# SCH_AUDIO5822.net
KiCad netlist of a schematic drawn in EasyEDA
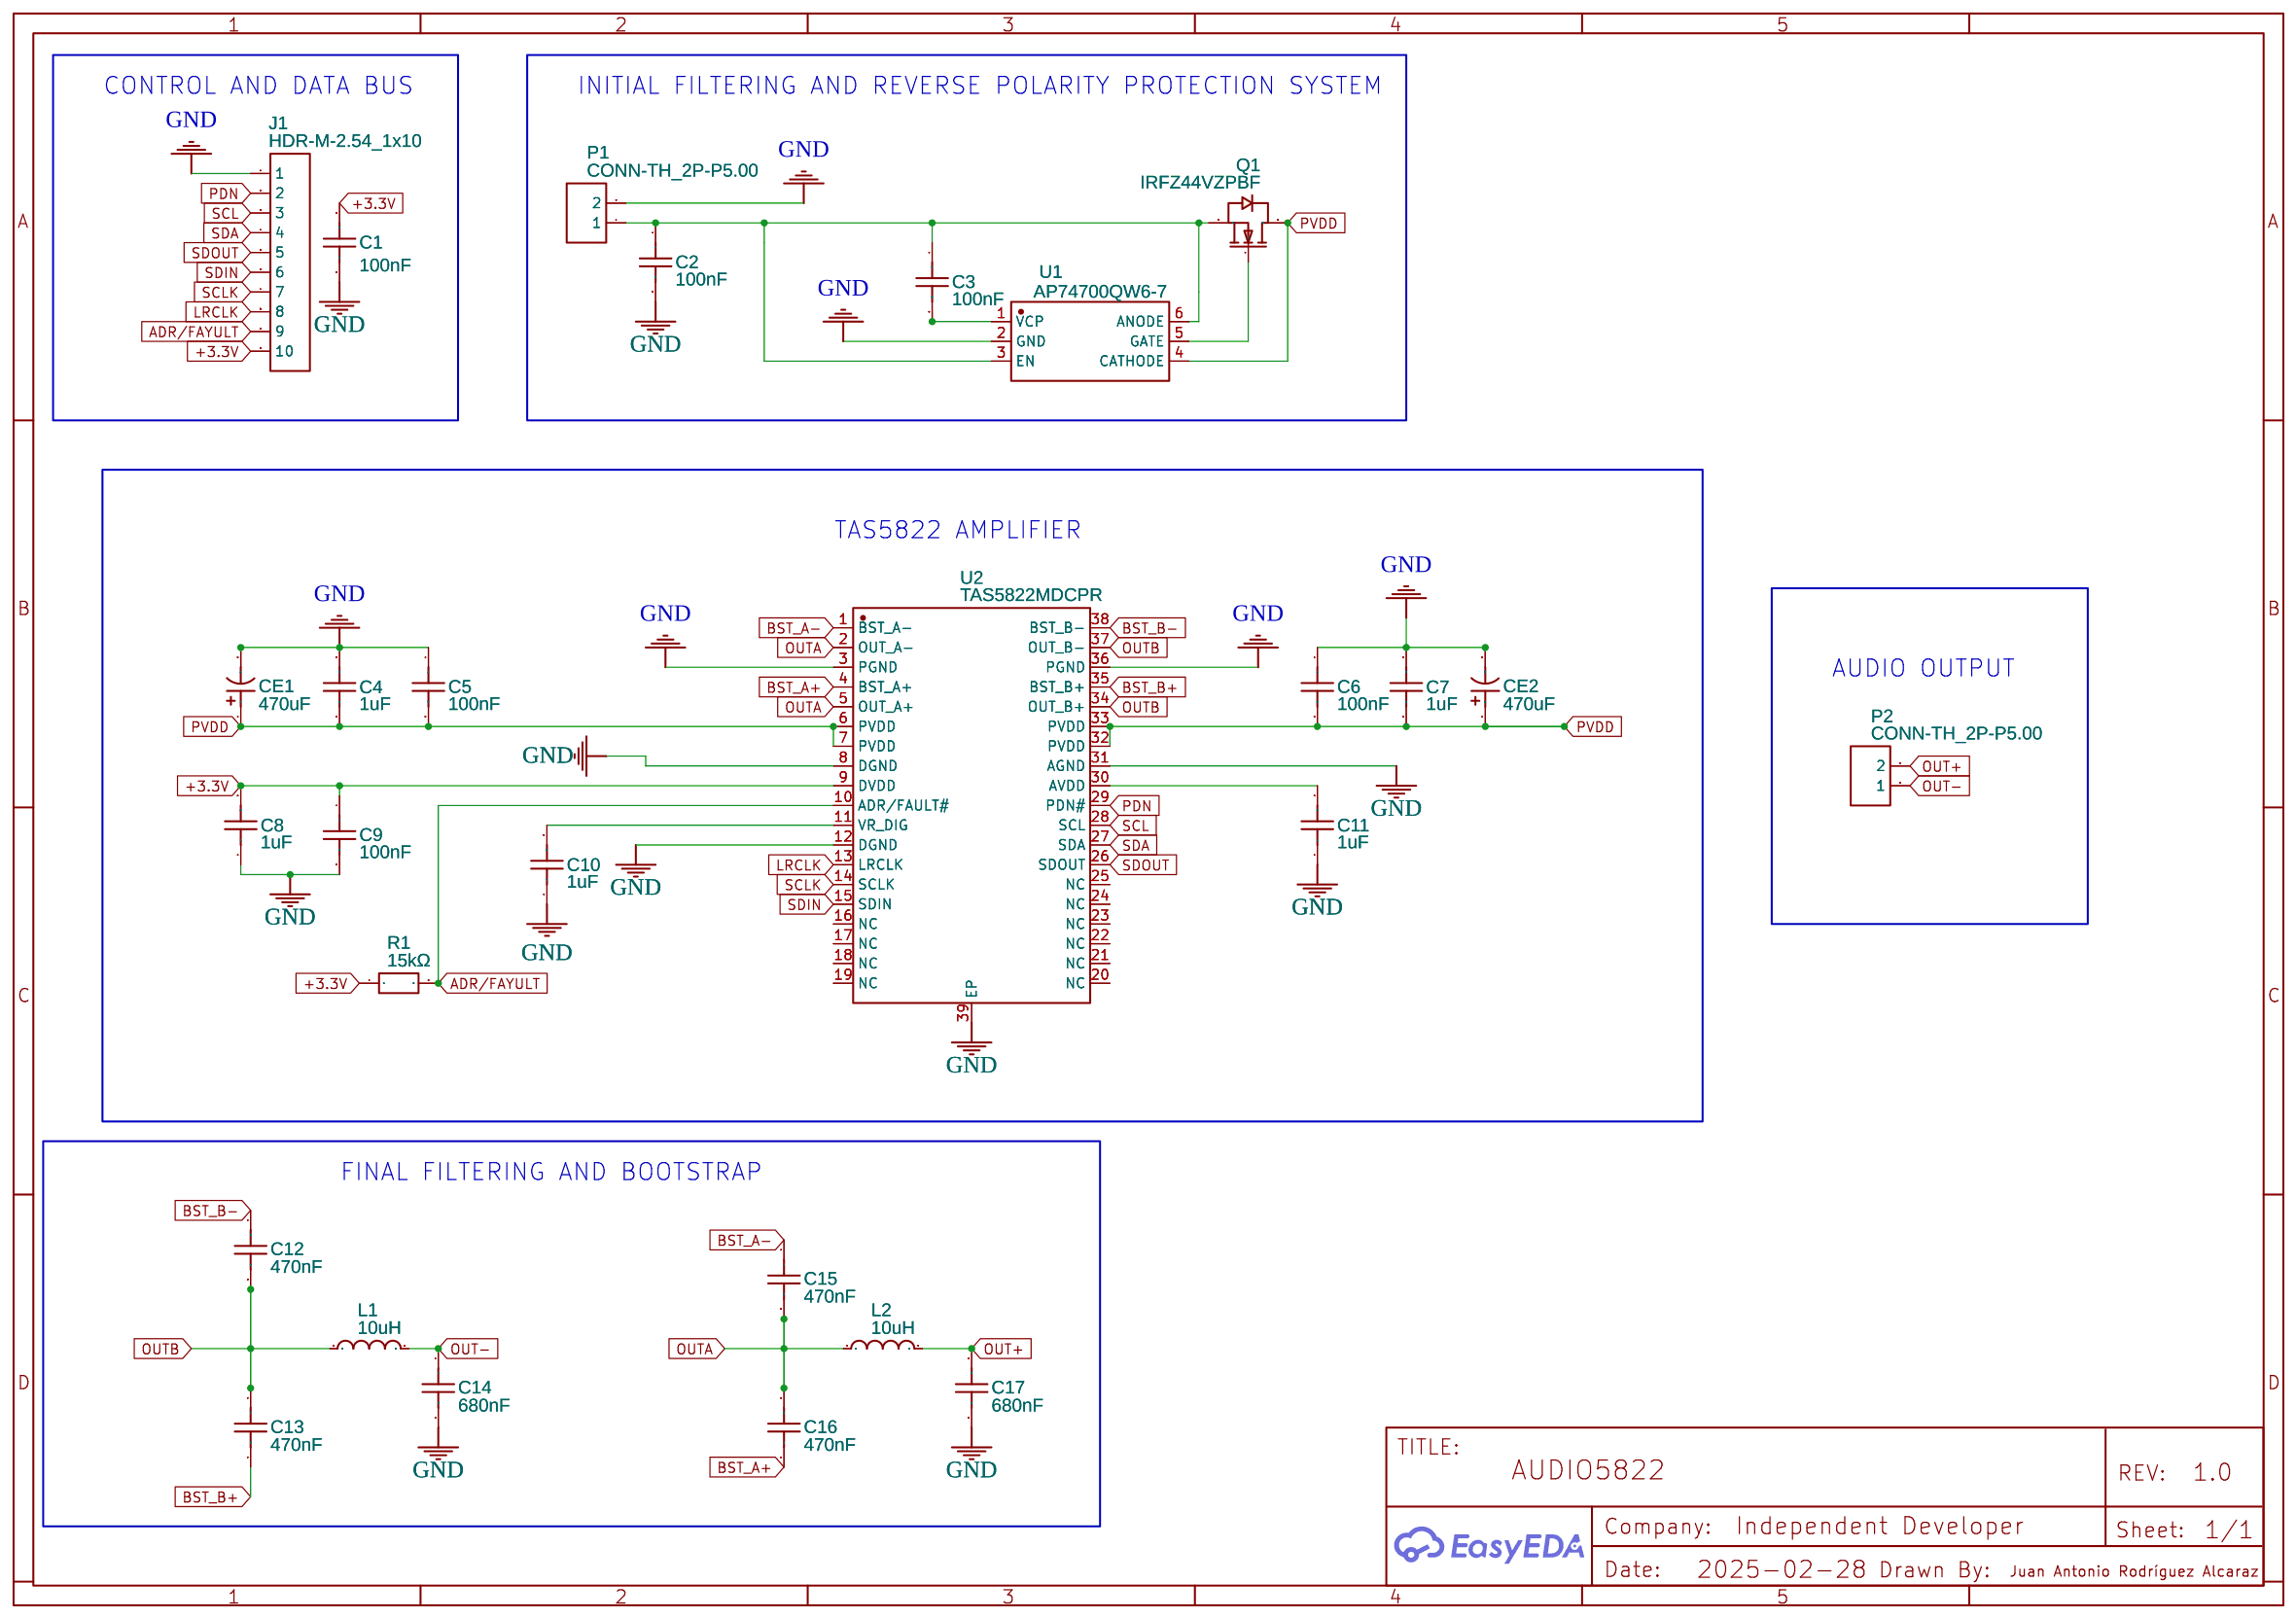
[diagram p0: schematic sheet]

(export (version "E")
  (design (tool "Eeschema 10.0.6"))
  (components
    (comp (ref "C1")
      (value "100nF")
      (fields (field (name "Manufacturer Part") "0603B104K101NT") (field (name "Manufacturer") "FH(风华)"))
      (libsource (lib "") (part "0603B104K101NT"))
    )
    (comp (ref "C2")
      (value "100nF")
      (fields (field (name "Manufacturer Part") "0603B104K101NT") (field (name "Manufacturer") "FH(风华)"))
      (libsource (lib "") (part "0603B104K101NT"))
    )
    (comp (ref "C3")
      (value "100nF")
      (fields (field (name "Manufacturer Part") "0603B104K101NT") (field (name "Manufacturer") "FH(风华)"))
      (libsource (lib "") (part "0603B104K101NT"))
    )
    (comp (ref "C4")
      (value "1uF")
      (fields (field (name "Manufacturer Part") "0603X105K500CT") (field (name "Manufacturer") "Walsin(华新科)"))
      (libsource (lib "") (part "0603X105K500"))
    )
    (comp (ref "C5")
      (value "100nF")
      (fields (field (name "Manufacturer Part") "0603B104K101NT") (field (name "Manufacturer") "FH(风华)"))
      (libsource (lib "") (part "0603B104K101NT"))
    )
    (comp (ref "C6")
      (value "100nF")
      (fields (field (name "Manufacturer Part") "0603B104K101NT") (field (name "Manufacturer") "FH(风华)"))
      (libsource (lib "") (part "0603B104K101NT"))
    )
    (comp (ref "C7")
      (value "1uF")
      (fields (field (name "Manufacturer Part") "0603X105K500CT") (field (name "Manufacturer") "Walsin(华新科)"))
      (libsource (lib "") (part "0603X105K500"))
    )
    (comp (ref "C8")
      (value "1uF")
      (fields (field (name "Manufacturer Part") "0603X105K500CT") (field (name "Manufacturer") "Walsin(华新科)"))
      (libsource (lib "") (part "0603X105K500"))
    )
    (comp (ref "C9")
      (value "100nF")
      (fields (field (name "Manufacturer Part") "0603B104K101NT") (field (name "Manufacturer") "FH(风华)"))
      (libsource (lib "") (part "0603B104K101NT"))
    )
    (comp (ref "C10")
      (value "1uF")
      (fields (field (name "Manufacturer Part") "0603X105K500CT") (field (name "Manufacturer") "Walsin(华新科)"))
      (libsource (lib "") (part "0603X105K500"))
    )
    (comp (ref "C11")
      (value "1uF")
      (fields (field (name "Manufacturer Part") "0603X105K500CT") (field (name "Manufacturer") "Walsin(华新科)"))
      (libsource (lib "") (part "0603X105K500"))
    )
    (comp (ref "C12")
      (value "470nF")
      (fields
        (field (name "Manufacturer Part") "HGC0603R7474K500NTHJ")
        (field (name "Manufacturer") "Chinocera(华瓷)")
      )
      (libsource (lib "") (part "HGC0603R7474K500NTHJ"))
    )
    (comp (ref "C13")
      (value "470nF")
      (fields
        (field (name "Manufacturer Part") "HGC0603R7474K500NTHJ")
        (field (name "Manufacturer") "Chinocera(华瓷)")
      )
      (libsource (lib "") (part "HGC0603R7474K500NTHJ"))
    )
    (comp (ref "C14")
      (value "680nF")
      (fields
        (field (name "Manufacturer Part") "TCC0603X7R684K500CT")
        (field (name "Manufacturer") "CCTC(三环)")
      )
      (libsource (lib "") (part "TCC0603X7R684K500CT"))
    )
    (comp (ref "C15")
      (value "470nF")
      (fields
        (field (name "Manufacturer Part") "HGC0603R7474K500NTHJ")
        (field (name "Manufacturer") "Chinocera(华瓷)")
      )
      (libsource (lib "") (part "HGC0603R7474K500NTHJ"))
    )
    (comp (ref "C16")
      (value "470nF")
      (fields
        (field (name "Manufacturer Part") "HGC0603R7474K500NTHJ")
        (field (name "Manufacturer") "Chinocera(华瓷)")
      )
      (libsource (lib "") (part "HGC0603R7474K500NTHJ"))
    )
    (comp (ref "C17")
      (value "680nF")
      (fields
        (field (name "Manufacturer Part") "TCC0603X7R684K500CT")
        (field (name "Manufacturer") "CCTC(三环)")
      )
      (libsource (lib "") (part "TCC0603X7R684K500CT"))
    )
    (comp (ref "CE1")
      (value "470uF")
      (fields (field (name "Manufacturer Part") "KM1V471M1016") (field (name "Manufacturer") "ROQANG(容强)"))
      (libsource (lib "") (part "KM1V471M1016_1"))
    )
    (comp (ref "CE2")
      (value "470uF")
      (fields (field (name "Manufacturer Part") "KM1V471M1016") (field (name "Manufacturer") "ROQANG(容强)"))
      (libsource (lib "") (part "KM1V471M1016"))
    )
    (comp (ref "J1") (value "HDR-M-2.54_1x10") (libsource (lib "") (part "HDR-M-2.54_1x10")))
    (comp (ref "L1")
      (value "10uH")
      (fields (field (name "Manufacturer Part") "APH1265T100M") (field (name "Manufacturer") "APV(爱普微)"))
      (libsource (lib "") (part "APH1265T100M"))
    )
    (comp (ref "L2")
      (value "10uH")
      (fields (field (name "Manufacturer Part") "APH1265T100M") (field (name "Manufacturer") "APV(爱普微)"))
      (libsource (lib "") (part "APH1265T100M"))
    )
    (comp (ref "P1") (value "CONN-TH_2P-P5.00") (libsource (lib "") (part "CONN-TH_2P-P5.00")))
    (comp (ref "P2") (value "CONN-TH_2P-P5.00") (libsource (lib "") (part "CONN-TH_2P-P5.00")))
    (comp (ref "Q1")
      (value "IRFZ44VZPBF")
      (fields (field (name "Manufacturer") "Infineon(英飞凌)"))
      (libsource (lib "") (part "IRFZ44VZPBF"))
    )
    (comp (ref "R1")
      (value "15kΩ")
      (fields (field (name "Manufacturer Part") "AF0402FR-0715KL") (field (name "Manufacturer") "YAGEO(国巨)"))
      (libsource (lib "") (part "AF0402FR-0715KL"))
    )
    (comp (ref "U1")
      (value "AP74700QW6-7")
      (fields (field (name "Manufacturer") "DIODES(美台)"))
      (libsource (lib "") (part "AP74700QW6-7"))
    )
    (comp (ref "U2")
      (value "TAS5822MDCPR")
      (fields (field (name "Manufacturer") "TI(德州仪器)"))
      (libsource (lib "") (part "TAS5822MDCPR"))
    )
  )
  (nets
    (net (code "1") (name "+3.3V") (class "Default")
      (node (ref "C1") (pin "1") (pinfunction "1_1") (pintype "unspecified"))
      (node (ref "C8") (pin "2") (pinfunction "2_2") (pintype "unspecified"))
      (node (ref "C9") (pin "1") (pinfunction "1_1") (pintype "unspecified"))
      (node (ref "J1") (pin "10") (pinfunction "10_10") (pintype "unspecified"))
      (node (ref "R1") (pin "1") (pinfunction "1_1") (pintype "unspecified"))
      (node (ref "U2") (pin "9") (pinfunction "DVDD_9") (pintype "unspecified"))
    )
    (net (code "2") (name "ADR{slash}FAYULT") (class "Default")
      (node (ref "J1") (pin "9") (pinfunction "9_9") (pintype "unspecified"))
      (node (ref "R1") (pin "2") (pinfunction "2_2") (pintype "unspecified"))
      (node (ref "U2") (pin "10") (pinfunction "ADR/FAULT#_10") (pintype "unspecified"))
    )
    (net (code "3") (name "BST_A+") (class "Default")
      (node (ref "C16") (pin "2") (pinfunction "2_2") (pintype "unspecified"))
      (node (ref "U2") (pin "4") (pinfunction "BST_A+_4") (pintype "unspecified"))
    )
    (net (code "4") (name "BST_A-") (class "Default")
      (node (ref "C15") (pin "1") (pinfunction "1_1") (pintype "unspecified"))
      (node (ref "U2") (pin "1") (pinfunction "BST_A-_1") (pintype "unspecified"))
    )
    (net (code "5") (name "BST_B+") (class "Default")
      (node (ref "C13") (pin "2") (pinfunction "2_2") (pintype "unspecified"))
      (node (ref "U2") (pin "35") (pinfunction "BST_B+_35") (pintype "unspecified"))
    )
    (net (code "6") (name "BST_B-") (class "Default")
      (node (ref "C12") (pin "1") (pinfunction "1_1") (pintype "unspecified"))
      (node (ref "U2") (pin "38") (pinfunction "BST_B-_38") (pintype "unspecified"))
    )
    (net (code "7") (name "GND") (class "Default")
      (node (ref "C1") (pin "2") (pinfunction "2_2") (pintype "unspecified"))
      (node (ref "C10") (pin "1") (pinfunction "1_1") (pintype "unspecified"))
      (node (ref "C11") (pin "1") (pinfunction "1_1") (pintype "unspecified"))
      (node (ref "C14") (pin "2") (pinfunction "2_2") (pintype "unspecified"))
      (node (ref "C17") (pin "2") (pinfunction "2_2") (pintype "unspecified"))
      (node (ref "C2") (pin "2") (pinfunction "2_2") (pintype "unspecified"))
      (node (ref "C4") (pin "2") (pinfunction "2_2") (pintype "unspecified"))
      (node (ref "C5") (pin "1") (pinfunction "1_1") (pintype "unspecified"))
      (node (ref "C6") (pin "1") (pinfunction "1_1") (pintype "unspecified"))
      (node (ref "C7") (pin "2") (pinfunction "2_2") (pintype "unspecified"))
      (node (ref "C8") (pin "1") (pinfunction "1_1") (pintype "unspecified"))
      (node (ref "C9") (pin "2") (pinfunction "2_2") (pintype "unspecified"))
      (node (ref "CE1") (pin "2") (pinfunction "2_2") (pintype "input"))
      (node (ref "CE2") (pin "2") (pinfunction "2_2") (pintype "input"))
      (node (ref "J1") (pin "1") (pinfunction "1_1") (pintype "unspecified"))
      (node (ref "P1") (pin "2") (pinfunction "2_2") (pintype "unspecified"))
      (node (ref "U1") (pin "2") (pinfunction "GND_2") (pintype "unspecified"))
      (node (ref "U2") (pin "12") (pinfunction "DGND_12") (pintype "unspecified"))
      (node (ref "U2") (pin "3") (pinfunction "PGND_3") (pintype "unspecified"))
      (node (ref "U2") (pin "31") (pinfunction "AGND_31") (pintype "unspecified"))
      (node (ref "U2") (pin "36") (pinfunction "PGND_36") (pintype "unspecified"))
      (node (ref "U2") (pin "39") (pinfunction "EP_39") (pintype "unspecified"))
      (node (ref "U2") (pin "8") (pinfunction "DGND_8") (pintype "unspecified"))
    )
    (net (code "8") (name "LRCLK") (class "Default")
      (node (ref "J1") (pin "8") (pinfunction "8_8") (pintype "unspecified"))
      (node (ref "U2") (pin "13") (pinfunction "LRCLK_13") (pintype "unspecified"))
    )
    (net (code "9") (name "Net-(Q1-G)") (class "Default")
      (node (ref "Q1") (pin "1") (pinfunction "G_1") (pintype "unspecified"))
      (node (ref "U1") (pin "5") (pinfunction "GATE_5") (pintype "unspecified"))
    )
    (net (code "10") (name "Net-(Q1-S)") (class "Default")
      (node (ref "C2") (pin "1") (pinfunction "1_1") (pintype "unspecified"))
      (node (ref "C3") (pin "1") (pinfunction "1_1") (pintype "unspecified"))
      (node (ref "P1") (pin "1") (pinfunction "1_1") (pintype "unspecified"))
      (node (ref "Q1") (pin "3") (pinfunction "S_3") (pintype "unspecified"))
      (node (ref "U1") (pin "3") (pinfunction "EN_3") (pintype "unspecified"))
      (node (ref "U1") (pin "6") (pinfunction "ANODE_6") (pintype "unspecified"))
    )
    (net (code "11") (name "Net-(U1-VCP)") (class "Default")
      (node (ref "C3") (pin "2") (pinfunction "2_2") (pintype "unspecified"))
      (node (ref "U1") (pin "1") (pinfunction "VCP_1") (pintype "unspecified"))
    )
    (net (code "12") (name "Net-(U2-AVDD)") (class "Default")
      (node (ref "C11") (pin "2") (pinfunction "2_2") (pintype "unspecified"))
      (node (ref "U2") (pin "30") (pinfunction "AVDD_30") (pintype "unspecified"))
    )
    (net (code "13") (name "Net-(U2-VR_DIG)") (class "Default")
      (node (ref "C10") (pin "2") (pinfunction "2_2") (pintype "unspecified"))
      (node (ref "U2") (pin "11") (pinfunction "VR_DIG_11") (pintype "unspecified"))
    )
    (net (code "14") (name "OUT+") (class "Default")
      (node (ref "C17") (pin "1") (pinfunction "1_1") (pintype "unspecified"))
      (node (ref "L2") (pin "2") (pinfunction "2_2") (pintype "unspecified"))
      (node (ref "P2") (pin "2") (pinfunction "2_2") (pintype "unspecified"))
    )
    (net (code "15") (name "OUT-") (class "Default")
      (node (ref "C14") (pin "1") (pinfunction "1_1") (pintype "unspecified"))
      (node (ref "L1") (pin "2") (pinfunction "2_2") (pintype "unspecified"))
      (node (ref "P2") (pin "1") (pinfunction "1_1") (pintype "unspecified"))
    )
    (net (code "16") (name "OUTA") (class "Default")
      (node (ref "C15") (pin "2") (pinfunction "2_2") (pintype "unspecified"))
      (node (ref "C16") (pin "1") (pinfunction "1_1") (pintype "unspecified"))
      (node (ref "L2") (pin "1") (pinfunction "1_1") (pintype "unspecified"))
      (node (ref "U2") (pin "2") (pinfunction "OUT_A-_2") (pintype "unspecified"))
      (node (ref "U2") (pin "5") (pinfunction "OUT_A+_5") (pintype "unspecified"))
    )
    (net (code "17") (name "OUTB") (class "Default")
      (node (ref "C12") (pin "2") (pinfunction "2_2") (pintype "unspecified"))
      (node (ref "C13") (pin "1") (pinfunction "1_1") (pintype "unspecified"))
      (node (ref "L1") (pin "1") (pinfunction "1_1") (pintype "unspecified"))
      (node (ref "U2") (pin "34") (pinfunction "OUT_B+_34") (pintype "unspecified"))
      (node (ref "U2") (pin "37") (pinfunction "OUT_B-_37") (pintype "unspecified"))
    )
    (net (code "18") (name "PDN") (class "Default")
      (node (ref "J1") (pin "2") (pinfunction "2_2") (pintype "unspecified"))
      (node (ref "U2") (pin "29") (pinfunction "PDN#_29") (pintype "unspecified"))
    )
    (net (code "19") (name "PVDD") (class "Default")
      (node (ref "C4") (pin "1") (pinfunction "1_1") (pintype "unspecified"))
      (node (ref "C5") (pin "2") (pinfunction "2_2") (pintype "unspecified"))
      (node (ref "C6") (pin "2") (pinfunction "2_2") (pintype "unspecified"))
      (node (ref "C7") (pin "1") (pinfunction "1_1") (pintype "unspecified"))
      (node (ref "CE1") (pin "1") (pinfunction "1_1") (pintype "input"))
      (node (ref "CE2") (pin "1") (pinfunction "1_1") (pintype "input"))
      (node (ref "Q1") (pin "2") (pinfunction "D_2") (pintype "unspecified"))
      (node (ref "U1") (pin "4") (pinfunction "CATHODE_4") (pintype "unspecified"))
      (node (ref "U2") (pin "32") (pinfunction "PVDD_32") (pintype "unspecified"))
      (node (ref "U2") (pin "33") (pinfunction "PVDD_33") (pintype "unspecified"))
      (node (ref "U2") (pin "6") (pinfunction "PVDD_6") (pintype "unspecified"))
      (node (ref "U2") (pin "7") (pinfunction "PVDD_7") (pintype "unspecified"))
    )
    (net (code "20") (name "SCL") (class "Default")
      (node (ref "J1") (pin "3") (pinfunction "3_3") (pintype "unspecified"))
      (node (ref "U2") (pin "28") (pinfunction "SCL_28") (pintype "unspecified"))
    )
    (net (code "21") (name "SCLK") (class "Default")
      (node (ref "J1") (pin "7") (pinfunction "7_7") (pintype "unspecified"))
      (node (ref "U2") (pin "14") (pinfunction "SCLK_14") (pintype "unspecified"))
    )
    (net (code "22") (name "SDA") (class "Default")
      (node (ref "J1") (pin "4") (pinfunction "4_4") (pintype "unspecified"))
      (node (ref "U2") (pin "27") (pinfunction "SDA_27") (pintype "unspecified"))
    )
    (net (code "23") (name "SDIN") (class "Default")
      (node (ref "J1") (pin "6") (pinfunction "6_6") (pintype "unspecified"))
      (node (ref "U2") (pin "15") (pinfunction "SDIN_15") (pintype "unspecified"))
    )
    (net (code "24") (name "SDOUT") (class "Default")
      (node (ref "J1") (pin "5") (pinfunction "5_5") (pintype "unspecified"))
      (node (ref "U2") (pin "26") (pinfunction "SDOUT_26") (pintype "unspecified"))
    )
    (net (code "25") (name "unconnected-(U2-NC-Pad16)") (class "Default")
      (node (ref "U2") (pin "16") (pinfunction "NC_16") (pintype "unspecified"))
    )
    (net (code "26") (name "unconnected-(U2-NC-Pad17)") (class "Default")
      (node (ref "U2") (pin "17") (pinfunction "NC_17") (pintype "unspecified"))
    )
    (net (code "27") (name "unconnected-(U2-NC-Pad18)") (class "Default")
      (node (ref "U2") (pin "18") (pinfunction "NC_18") (pintype "unspecified"))
    )
    (net (code "28") (name "unconnected-(U2-NC-Pad19)") (class "Default")
      (node (ref "U2") (pin "19") (pinfunction "NC_19") (pintype "unspecified"))
    )
    (net (code "29") (name "unconnected-(U2-NC-Pad20)") (class "Default")
      (node (ref "U2") (pin "20") (pinfunction "NC_20") (pintype "unspecified"))
    )
    (net (code "30") (name "unconnected-(U2-NC-Pad21)") (class "Default")
      (node (ref "U2") (pin "21") (pinfunction "NC_21") (pintype "unspecified"))
    )
    (net (code "31") (name "unconnected-(U2-NC-Pad22)") (class "Default")
      (node (ref "U2") (pin "22") (pinfunction "NC_22") (pintype "unspecified"))
    )
    (net (code "32") (name "unconnected-(U2-NC-Pad23)") (class "Default")
      (node (ref "U2") (pin "23") (pinfunction "NC_23") (pintype "unspecified"))
    )
    (net (code "33") (name "unconnected-(U2-NC-Pad24)") (class "Default")
      (node (ref "U2") (pin "24") (pinfunction "NC_24") (pintype "unspecified"))
    )
    (net (code "34") (name "unconnected-(U2-NC-Pad25)") (class "Default")
      (node (ref "U2") (pin "25") (pinfunction "NC_25") (pintype "unspecified"))
    )
  )
)
